# 4_STM32.net
KiCad netlist of a schematic drawn in Altium Designer
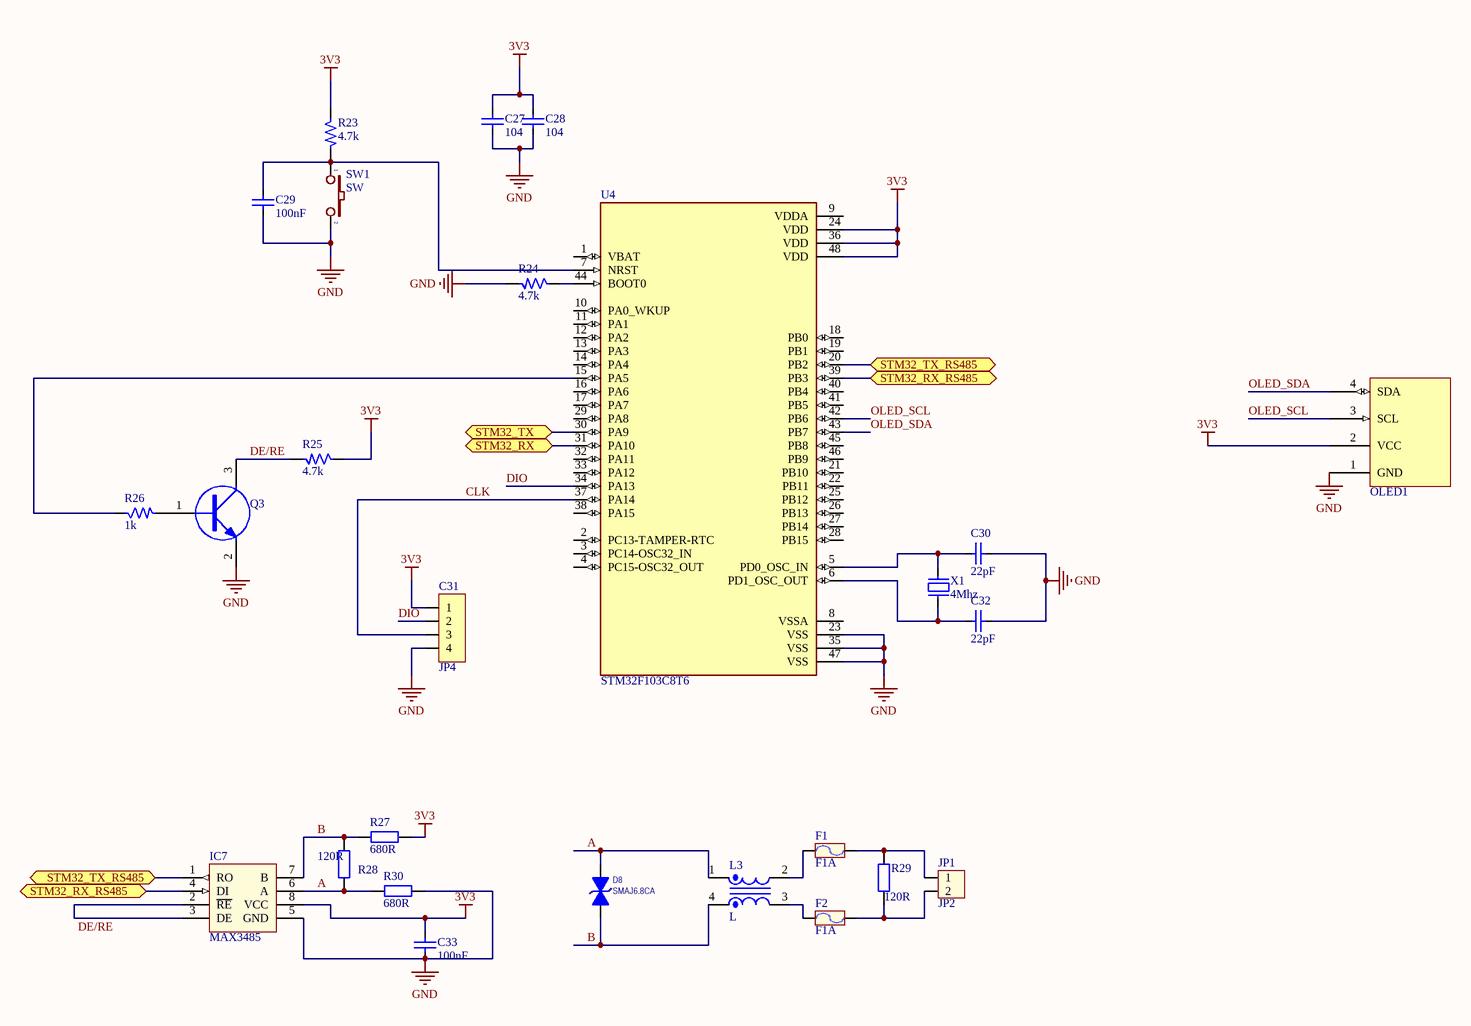
[diagram p0: 4.STM32.SchDoc]

(export (version "E")
  (design (tool "Eeschema 10.0.6"))
  (components
    (comp (ref "C27")
      (value "104")
      (footprint "CAP_0805")
      (description "Capacitor")
      (fields (field (name "PUBLISHER") "Altium Limited"))
      (libsource (lib "My-Library") (part "CapSMD"))
    )
    (comp (ref "C28")
      (value "104")
      (footprint "CAP_0805")
      (description "Capacitor")
      (fields (field (name "PUBLISHER") "Altium Limited"))
      (libsource (lib "My-Library") (part "CapSMD"))
    )
    (comp (ref "C29")
      (value "100nF")
      (footprint "CAP_0805")
      (description "Capacitor")
      (fields (field (name "PUBLISHER") "Altium Limited"))
      (libsource (lib "My-Library") (part "CapSMD"))
    )
    (comp (ref "C30")
      (value "22pF")
      (footprint "CAP_0805")
      (description "Capacitor")
      (fields (field (name "PUBLISHER") "Altium Limited"))
      (libsource (lib "My-Library") (part "CapSMD"))
    )
    (comp (ref "C31")
      (value "JP4")
      (footprint "JP4-C1T")
      (description "WR-PHD 2.54 mm Angled Socket Header")
      (fields
        (field (name "MANUFACTURER") "Würth Elektronik eiSos GmbH")
        (field (name "PARTNO") "613004143121")
        (field (name "CREATED BY") "Karrer Zheng")
      )
      (libsource (lib "My-Library") (part "JP4"))
    )
    (comp (ref "C32")
      (value "22pF")
      (footprint "CAP_0805")
      (description "Capacitor")
      (fields (field (name "PUBLISHER") "Altium Limited"))
      (libsource (lib "My-Library") (part "CapSMD"))
    )
    (comp (ref "C33")
      (value "100nF")
      (footprint "CAP_0805")
      (description "Capacitor")
      (fields (field (name "PUBLISHER") "Altium Limited"))
      (libsource (lib "My-Library") (part "CapSMD"))
    )
    (comp (ref "D8")
      (value "SMAJ6.8CA")
      (footprint "SOD323 - DO241")
      (description "TVS DIODE 30VWM 48.4VC SMA")
      (fields (field (name "MANUFACTURER") "Bourns Inc.") (field (name "PART NUMBER") "PSD12C"))
      (libsource (lib "Anh_Trung") (part "SMAJ30CA-30V/8.3A"))
    )
    (comp (ref "F1")
      (value "F1A")
      (footprint "RES-SMD-1206")
      (description "F smd1206 0.315A")
      (fields (field (name "DESIGNED BY") "VanDungEvn"))
      (libsource (lib "Main") (part "Fuse"))
    )
    (comp (ref "F2")
      (value "F1A")
      (footprint "RES-SMD-1206")
      (description "F smd1206 0.315A")
      (fields (field (name "DESIGNED BY") "VanDungEvn"))
      (libsource (lib "Main") (part "Fuse"))
    )
    (comp (ref "IC7")
      (value "MAX3485")
      (footprint "SOIC-8")
      (description "IC TRANSCEIVER HALF 1/1 SOT23-8")
      (fields (field (name "MANUFACTURER") "Maxim Integrated") (field (name "PART NUMBER") "MAX3362EKA+T"))
      (libsource (lib "Anh_Trung") (part "MAX3362EKA+T"))
    )
    (comp (ref "JP1")
      (value "JP2")
      (footprint "KF2-5.08")
      (description "Connector 2")
      (libsource (lib "Anh_Trung") (part "Con2"))
    )
    (comp (ref "L3")
      (value "L")
      (footprint "L-B82793S0513N201")
      (description "CMC 51UH 800MA 2LN SMD AEC-Q200")
      (fields
        (field (name "MANUFACTURER") "EPCOS - TDK Electronics")
        (field (name "PART NUMBER") "B82793S0513N201")
      )
      (libsource (lib "SIM_devkit") (part "L filter Common Mode Chokes"))
    )
    (comp (ref "OLED1")
      (value "SSD1306")
      (footprint "OLED 1.3")
      (description "OLED 1.3\" SSD1306")
      (libsource (lib "My-Library") (part "OLED 1.3{dblquote}"))
    )
    (comp (ref "Q3")
      (value "C1815(MMBT4401)")
      (footprint "SOT23")
      (description "Transistor C1815, SOT23")
      (fields (field (name "MANUFACTURER") "Fairchild Semiconductor") (field (name "PART NUMBER") "MMBT4401"))
      (libsource (lib "Anh_Trung") (part "NPN"))
    )
    (comp (ref "R23")
      (value "4.7k")
      (footprint "R-0805")
      (description "RES SMD 4.7K OHM 1% 1/8W 0805")
      (fields (field (name "MANUFACTURER") "Yageo") (field (name "PART NUMBER") "RC0805FR-074K7L"))
      (libsource (lib "Anh_Trung") (part "R"))
    )
    (comp (ref "R24")
      (value "4.7k")
      (footprint "R-0805")
      (description "RES SMD 4.7K OHM 1% 1/8W 0805")
      (fields (field (name "MANUFACTURER") "Yageo") (field (name "PART NUMBER") "RC0805FR-074K7L"))
      (libsource (lib "Anh_Trung") (part "R"))
    )
    (comp (ref "R25")
      (value "4.7k")
      (footprint "R-0805")
      (description "RES SMD 4.7K OHM 1% 1/8W 0805")
      (fields (field (name "MANUFACTURER") "Yageo") (field (name "PART NUMBER") "RC0805FR-074K7L"))
      (libsource (lib "Anh_Trung") (part "R"))
    )
    (comp (ref "R26")
      (value "1k")
      (footprint "R-0805")
      (description "Resistor 1/4W")
      (fields (field (name "MANUFACTURER") "Yageo") (field (name "PART NUMBER") "RC0805FR-071KL"))
      (libsource (lib "Anh_Trung") (part "R"))
    )
    (comp (ref "R27")
      (value "680R")
      (footprint "RES-SMD-0805")
      (description "Resistor SMD")
      (fields
        (field (name "MANUFACTURER") "Generic Components")
        (field (name "PUBLISHER") "Altium Hobart Technology Centre")
      )
      (libsource (lib "Main") (part "Resistor - SMD"))
    )
    (comp (ref "R28")
      (value "120R")
      (footprint "RES-SMD-0805")
      (description "Resistor SMD")
      (fields
        (field (name "MANUFACTURER") "Generic Components")
        (field (name "PUBLISHER") "Altium Hobart Technology Centre")
      )
      (libsource (lib "Main") (part "Resistor - SMD"))
    )
    (comp (ref "R29")
      (value "120R")
      (footprint "RES-SMD-0805")
      (description "Resistor SMD")
      (fields
        (field (name "MANUFACTURER") "Generic Components")
        (field (name "PUBLISHER") "Altium Hobart Technology Centre")
      )
      (libsource (lib "Main") (part "Resistor - SMD"))
    )
    (comp (ref "R30")
      (value "680R")
      (footprint "RES-SMD-0805")
      (description "Resistor SMD")
      (fields
        (field (name "MANUFACTURER") "Generic Components")
        (field (name "PUBLISHER") "Altium Hobart Technology Centre")
      )
      (libsource (lib "Main") (part "Resistor - SMD"))
    )
    (comp (ref "SW1")
      (value "SW")
      (footprint "SW2")
      (description "Switch button 2 pin")
      (libsource (lib "My-Library") (part "SW2"))
    )
    (comp (ref "U4")
      (value "STM32F103C8T6")
      (footprint "STM32F103C8T6")
      (libsource (lib "My-Library") (part "STM32F103C8T6"))
    )
    (comp (ref "X1")
      (value "4Mhz")
      (footprint "XT2")
      (description "Crystal For all Crystal 2pin.")
      (libsource (lib "My-Library") (part "XT2"))
    )
  )
  (nets
    (net (code "1") (name "/A") (class "Default")
      (node (ref "D8") (pin "2") (pinfunction "K_2") (pintype "passive"))
      (node (ref "IC7") (pin "6") (pinfunction "A_6") (pintype "passive"))
      (node (ref "L3") (pin "1") (pintype "passive"))
      (node (ref "R28") (pin "2") (pinfunction "2_2") (pintype "passive"))
      (node (ref "R30") (pin "1") (pinfunction "1_1") (pintype "passive"))
    )
    (net (code "2") (name "/B") (class "Default")
      (node (ref "D8") (pin "1") (pinfunction "A_1") (pintype "passive"))
      (node (ref "IC7") (pin "7") (pinfunction "B_7") (pintype "passive"))
      (node (ref "L3") (pin "4") (pintype "passive"))
      (node (ref "R27") (pin "1") (pinfunction "1_1") (pintype "passive"))
      (node (ref "R28") (pin "1") (pinfunction "1_1") (pintype "passive"))
    )
    (net (code "3") (name "/CLK") (class "Default")
      (node (ref "C31") (pin "3") (pinfunction "3_3") (pintype "passive"))
      (node (ref "U4") (pin "37") (pinfunction "PA14_37") (pintype "bidirectional"))
    )
    (net (code "4") (name "/DE{slash}RE") (class "Default")
      (node (ref "IC7") (pin "2") (pinfunction "~{RE}_2") (pintype "passive"))
      (node (ref "IC7") (pin "3") (pinfunction "DE_3") (pintype "passive"))
      (node (ref "Q3") (pin "3") (pinfunction "C_3") (pintype "passive"))
      (node (ref "R25") (pin "2") (pinfunction "2_2") (pintype "passive"))
    )
    (net (code "5") (name "/DIO") (class "Default")
      (node (ref "C31") (pin "2") (pinfunction "2_2") (pintype "passive"))
      (node (ref "U4") (pin "34") (pinfunction "PA13_34") (pintype "bidirectional"))
    )
    (net (code "6") (name "/OLED_SCL") (class "Default")
      (node (ref "OLED1") (pin "3") (pinfunction "SCL_3") (pintype "input"))
      (node (ref "U4") (pin "42") (pinfunction "PB6_42") (pintype "bidirectional"))
    )
    (net (code "7") (name "/OLED_SDA") (class "Default")
      (node (ref "OLED1") (pin "4") (pinfunction "SDA_4") (pintype "bidirectional"))
      (node (ref "U4") (pin "43") (pinfunction "PB7_43") (pintype "bidirectional"))
    )
    (net (code "8") (name "/STM32_RX") (class "Default")
      (node (ref "U4") (pin "31") (pinfunction "PA10_31") (pintype "bidirectional"))
    )
    (net (code "9") (name "/STM32_RX_RS485") (class "Default")
      (node (ref "IC7") (pin "4") (pinfunction "DI_4") (pintype "input"))
      (node (ref "U4") (pin "39") (pinfunction "PB3_39") (pintype "bidirectional"))
    )
    (net (code "10") (name "/STM32_TX") (class "Default")
      (node (ref "U4") (pin "30") (pinfunction "PA9_30") (pintype "bidirectional"))
    )
    (net (code "11") (name "/STM32_TX_RS485") (class "Default")
      (node (ref "IC7") (pin "1") (pinfunction "RO_1") (pintype "output"))
      (node (ref "U4") (pin "20") (pinfunction "PB2_20") (pintype "bidirectional"))
    )
    (net (code "12") (name "3V3") (class "Default")
      (node (ref "C27") (pin "1") (pinfunction "1_1") (pintype "passive"))
      (node (ref "C28") (pin "1") (pinfunction "1_1") (pintype "passive"))
      (node (ref "C31") (pin "1") (pinfunction "1_1") (pintype "passive"))
      (node (ref "C33") (pin "1") (pinfunction "1_1") (pintype "passive"))
      (node (ref "IC7") (pin "8") (pinfunction "VCC_8") (pintype "passive"))
      (node (ref "OLED1") (pin "2") (pinfunction "VCC_2") (pintype "power_in"))
      (node (ref "R23") (pin "1") (pinfunction "1_1") (pintype "passive"))
      (node (ref "R25") (pin "1") (pinfunction "1_1") (pintype "passive"))
      (node (ref "R27") (pin "2") (pinfunction "2_2") (pintype "passive"))
      (node (ref "U4") (pin "24") (pinfunction "VDD_24") (pintype "power_in"))
      (node (ref "U4") (pin "36") (pinfunction "VDD_36") (pintype "power_in"))
      (node (ref "U4") (pin "48") (pinfunction "VDD_48") (pintype "power_in"))
    )
    (net (code "13") (name "GND") (class "Default")
      (node (ref "C27") (pin "2") (pinfunction "2_2") (pintype "passive"))
      (node (ref "C28") (pin "2") (pinfunction "2_2") (pintype "passive"))
      (node (ref "C29") (pin "2") (pinfunction "2_2") (pintype "passive"))
      (node (ref "C30") (pin "1") (pinfunction "1_1") (pintype "passive"))
      (node (ref "C31") (pin "4") (pinfunction "4_4") (pintype "passive"))
      (node (ref "C32") (pin "1") (pinfunction "1_1") (pintype "passive"))
      (node (ref "C33") (pin "2") (pinfunction "2_2") (pintype "passive"))
      (node (ref "IC7") (pin "5") (pinfunction "GND_5") (pintype "passive"))
      (node (ref "OLED1") (pin "1") (pinfunction "GND_1") (pintype "power_in"))
      (node (ref "Q3") (pin "2") (pinfunction "E_2") (pintype "passive"))
      (node (ref "R24") (pin "2") (pinfunction "2_2") (pintype "passive"))
      (node (ref "R30") (pin "2") (pinfunction "2_2") (pintype "passive"))
      (node (ref "SW1") (pin "2") (pinfunction "2_2") (pintype "passive"))
      (node (ref "U4") (pin "23") (pinfunction "VSS_23") (pintype "power_in"))
      (node (ref "U4") (pin "35") (pinfunction "VSS_35") (pintype "power_in"))
      (node (ref "U4") (pin "47") (pinfunction "VSS_47") (pintype "power_in"))
    )
    (net (code "14") (name "Net-(F1-Pad1)") (class "Default")
      (node (ref "F1") (pin "1") (pinfunction "1_1") (pintype "passive"))
      (node (ref "L3") (pin "2") (pintype "passive"))
    )
    (net (code "15") (name "Net-(F1-Pad2)") (class "Default")
      (node (ref "F1") (pin "2") (pinfunction "2_2") (pintype "passive"))
      (node (ref "JP1") (pin "1") (pinfunction "1_1") (pintype "passive"))
      (node (ref "R29") (pin "1") (pinfunction "1_1") (pintype "passive"))
    )
    (net (code "16") (name "Net-(F2-Pad1)") (class "Default")
      (node (ref "F2") (pin "1") (pinfunction "1_1") (pintype "passive"))
      (node (ref "L3") (pin "3") (pintype "passive"))
    )
    (net (code "17") (name "Net-(F2-Pad2)") (class "Default")
      (node (ref "F2") (pin "2") (pinfunction "2_2") (pintype "passive"))
      (node (ref "JP1") (pin "2") (pinfunction "2_2") (pintype "passive"))
      (node (ref "R29") (pin "2") (pinfunction "2_2") (pintype "passive"))
    )
    (net (code "18") (name "Net-(Q3-B)") (class "Default")
      (node (ref "Q3") (pin "1") (pinfunction "B_1") (pintype "passive"))
      (node (ref "R26") (pin "2") (pinfunction "2_2") (pintype "passive"))
    )
    (net (code "19") (name "Net-(U4-BOOT0)") (class "Default")
      (node (ref "R24") (pin "1") (pinfunction "1_1") (pintype "passive"))
      (node (ref "U4") (pin "44") (pinfunction "BOOT0_44") (pintype "input"))
    )
    (net (code "20") (name "Net-(U4-NRST)") (class "Default")
      (node (ref "C29") (pin "1") (pinfunction "1_1") (pintype "passive"))
      (node (ref "R23") (pin "2") (pinfunction "2_2") (pintype "passive"))
      (node (ref "SW1") (pin "1") (pinfunction "1_1") (pintype "passive"))
      (node (ref "U4") (pin "7") (pinfunction "NRST_7") (pintype "input"))
    )
    (net (code "21") (name "Net-(U4-PA5)") (class "Default")
      (node (ref "R26") (pin "1") (pinfunction "1_1") (pintype "passive"))
      (node (ref "U4") (pin "15") (pinfunction "PA5_15") (pintype "bidirectional"))
    )
    (net (code "22") (name "Net-(U4-PD0_OSC_IN)") (class "Default")
      (node (ref "C30") (pin "2") (pinfunction "2_2") (pintype "passive"))
      (node (ref "U4") (pin "5") (pinfunction "PD0_OSC_IN_5") (pintype "bidirectional"))
      (node (ref "X1") (pin "2") (pinfunction "2_2") (pintype "passive"))
    )
    (net (code "23") (name "Net-(U4-PD1_OSC_OUT)") (class "Default")
      (node (ref "C32") (pin "2") (pinfunction "2_2") (pintype "passive"))
      (node (ref "U4") (pin "6") (pinfunction "PD1_OSC_OUT_6") (pintype "bidirectional"))
      (node (ref "X1") (pin "1") (pinfunction "1_1") (pintype "passive"))
    )
    (net (code "24") (name "unconnected-(U4-PA0_WKUP-Pad10)") (class "Default")
      (node (ref "U4") (pin "10") (pinfunction "PA0_WKUP_10") (pintype "bidirectional"))
    )
    (net (code "25") (name "unconnected-(U4-PA1-Pad11)") (class "Default")
      (node (ref "U4") (pin "11") (pinfunction "PA1_11") (pintype "bidirectional"))
    )
    (net (code "26") (name "unconnected-(U4-PA2-Pad12)") (class "Default")
      (node (ref "U4") (pin "12") (pinfunction "PA2_12") (pintype "bidirectional"))
    )
    (net (code "27") (name "unconnected-(U4-PA3-Pad13)") (class "Default")
      (node (ref "U4") (pin "13") (pinfunction "PA3_13") (pintype "bidirectional"))
    )
    (net (code "28") (name "unconnected-(U4-PA4-Pad14)") (class "Default")
      (node (ref "U4") (pin "14") (pinfunction "PA4_14") (pintype "bidirectional"))
    )
    (net (code "29") (name "unconnected-(U4-PA6-Pad16)") (class "Default")
      (node (ref "U4") (pin "16") (pinfunction "PA6_16") (pintype "bidirectional"))
    )
    (net (code "30") (name "unconnected-(U4-PA7-Pad17)") (class "Default")
      (node (ref "U4") (pin "17") (pinfunction "PA7_17") (pintype "bidirectional"))
    )
    (net (code "31") (name "unconnected-(U4-PA8-Pad29)") (class "Default")
      (node (ref "U4") (pin "29") (pinfunction "PA8_29") (pintype "bidirectional"))
    )
    (net (code "32") (name "unconnected-(U4-PA11-Pad32)") (class "Default")
      (node (ref "U4") (pin "32") (pinfunction "PA11_32") (pintype "bidirectional"))
    )
    (net (code "33") (name "unconnected-(U4-PA12-Pad33)") (class "Default")
      (node (ref "U4") (pin "33") (pinfunction "PA12_33") (pintype "bidirectional"))
    )
    (net (code "34") (name "unconnected-(U4-PA15-Pad38)") (class "Default")
      (node (ref "U4") (pin "38") (pinfunction "PA15_38") (pintype "bidirectional"))
    )
    (net (code "35") (name "unconnected-(U4-PB0-Pad18)") (class "Default")
      (node (ref "U4") (pin "18") (pinfunction "PB0_18") (pintype "bidirectional"))
    )
    (net (code "36") (name "unconnected-(U4-PB1-Pad19)") (class "Default")
      (node (ref "U4") (pin "19") (pinfunction "PB1_19") (pintype "bidirectional"))
    )
    (net (code "37") (name "unconnected-(U4-PB4-Pad40)") (class "Default")
      (node (ref "U4") (pin "40") (pinfunction "PB4_40") (pintype "bidirectional"))
    )
    (net (code "38") (name "unconnected-(U4-PB5-Pad41)") (class "Default")
      (node (ref "U4") (pin "41") (pinfunction "PB5_41") (pintype "bidirectional"))
    )
    (net (code "39") (name "unconnected-(U4-PB8-Pad45)") (class "Default")
      (node (ref "U4") (pin "45") (pinfunction "PB8_45") (pintype "bidirectional"))
    )
    (net (code "40") (name "unconnected-(U4-PB9-Pad46)") (class "Default")
      (node (ref "U4") (pin "46") (pinfunction "PB9_46") (pintype "bidirectional"))
    )
    (net (code "41") (name "unconnected-(U4-PB10-Pad21)") (class "Default")
      (node (ref "U4") (pin "21") (pinfunction "PB10_21") (pintype "bidirectional"))
    )
    (net (code "42") (name "unconnected-(U4-PB11-Pad22)") (class "Default")
      (node (ref "U4") (pin "22") (pinfunction "PB11_22") (pintype "bidirectional"))
    )
    (net (code "43") (name "unconnected-(U4-PB12-Pad25)") (class "Default")
      (node (ref "U4") (pin "25") (pinfunction "PB12_25") (pintype "bidirectional"))
    )
    (net (code "44") (name "unconnected-(U4-PB13-Pad26)") (class "Default")
      (node (ref "U4") (pin "26") (pinfunction "PB13_26") (pintype "bidirectional"))
    )
    (net (code "45") (name "unconnected-(U4-PB14-Pad27)") (class "Default")
      (node (ref "U4") (pin "27") (pinfunction "PB14_27") (pintype "bidirectional"))
    )
    (net (code "46") (name "unconnected-(U4-PB15-Pad28)") (class "Default")
      (node (ref "U4") (pin "28") (pinfunction "PB15_28") (pintype "bidirectional"))
    )
    (net (code "47") (name "unconnected-(U4-PC13-TAMPER-RTC-Pad2)") (class "Default")
      (node (ref "U4") (pin "2") (pinfunction "PC13-TAMPER-RTC_2") (pintype "bidirectional"))
    )
    (net (code "48") (name "unconnected-(U4-PC14-OSC32_IN-Pad3)") (class "Default")
      (node (ref "U4") (pin "3") (pinfunction "PC14-OSC32_IN_3") (pintype "bidirectional"))
    )
    (net (code "49") (name "unconnected-(U4-PC15-OSC32_OUT-Pad4)") (class "Default")
      (node (ref "U4") (pin "4") (pinfunction "PC15-OSC32_OUT_4") (pintype "bidirectional"))
    )
    (net (code "50") (name "unconnected-(U4-VBAT-Pad1)") (class "Default")
      (node (ref "U4") (pin "1") (pinfunction "VBAT_1") (pintype "bidirectional"))
    )
    (net (code "51") (name "unconnected-(U4-VDDA-Pad9)") (class "Default")
      (node (ref "U4") (pin "9") (pinfunction "VDDA_9") (pintype "power_in"))
    )
    (net (code "52") (name "unconnected-(U4-VSSA-Pad8)") (class "Default")
      (node (ref "U4") (pin "8") (pinfunction "VSSA_8") (pintype "power_in"))
    )
  )
)
